# block_detector_schematic.net
KiCad netlist of a schematic drawn in EasyEDA
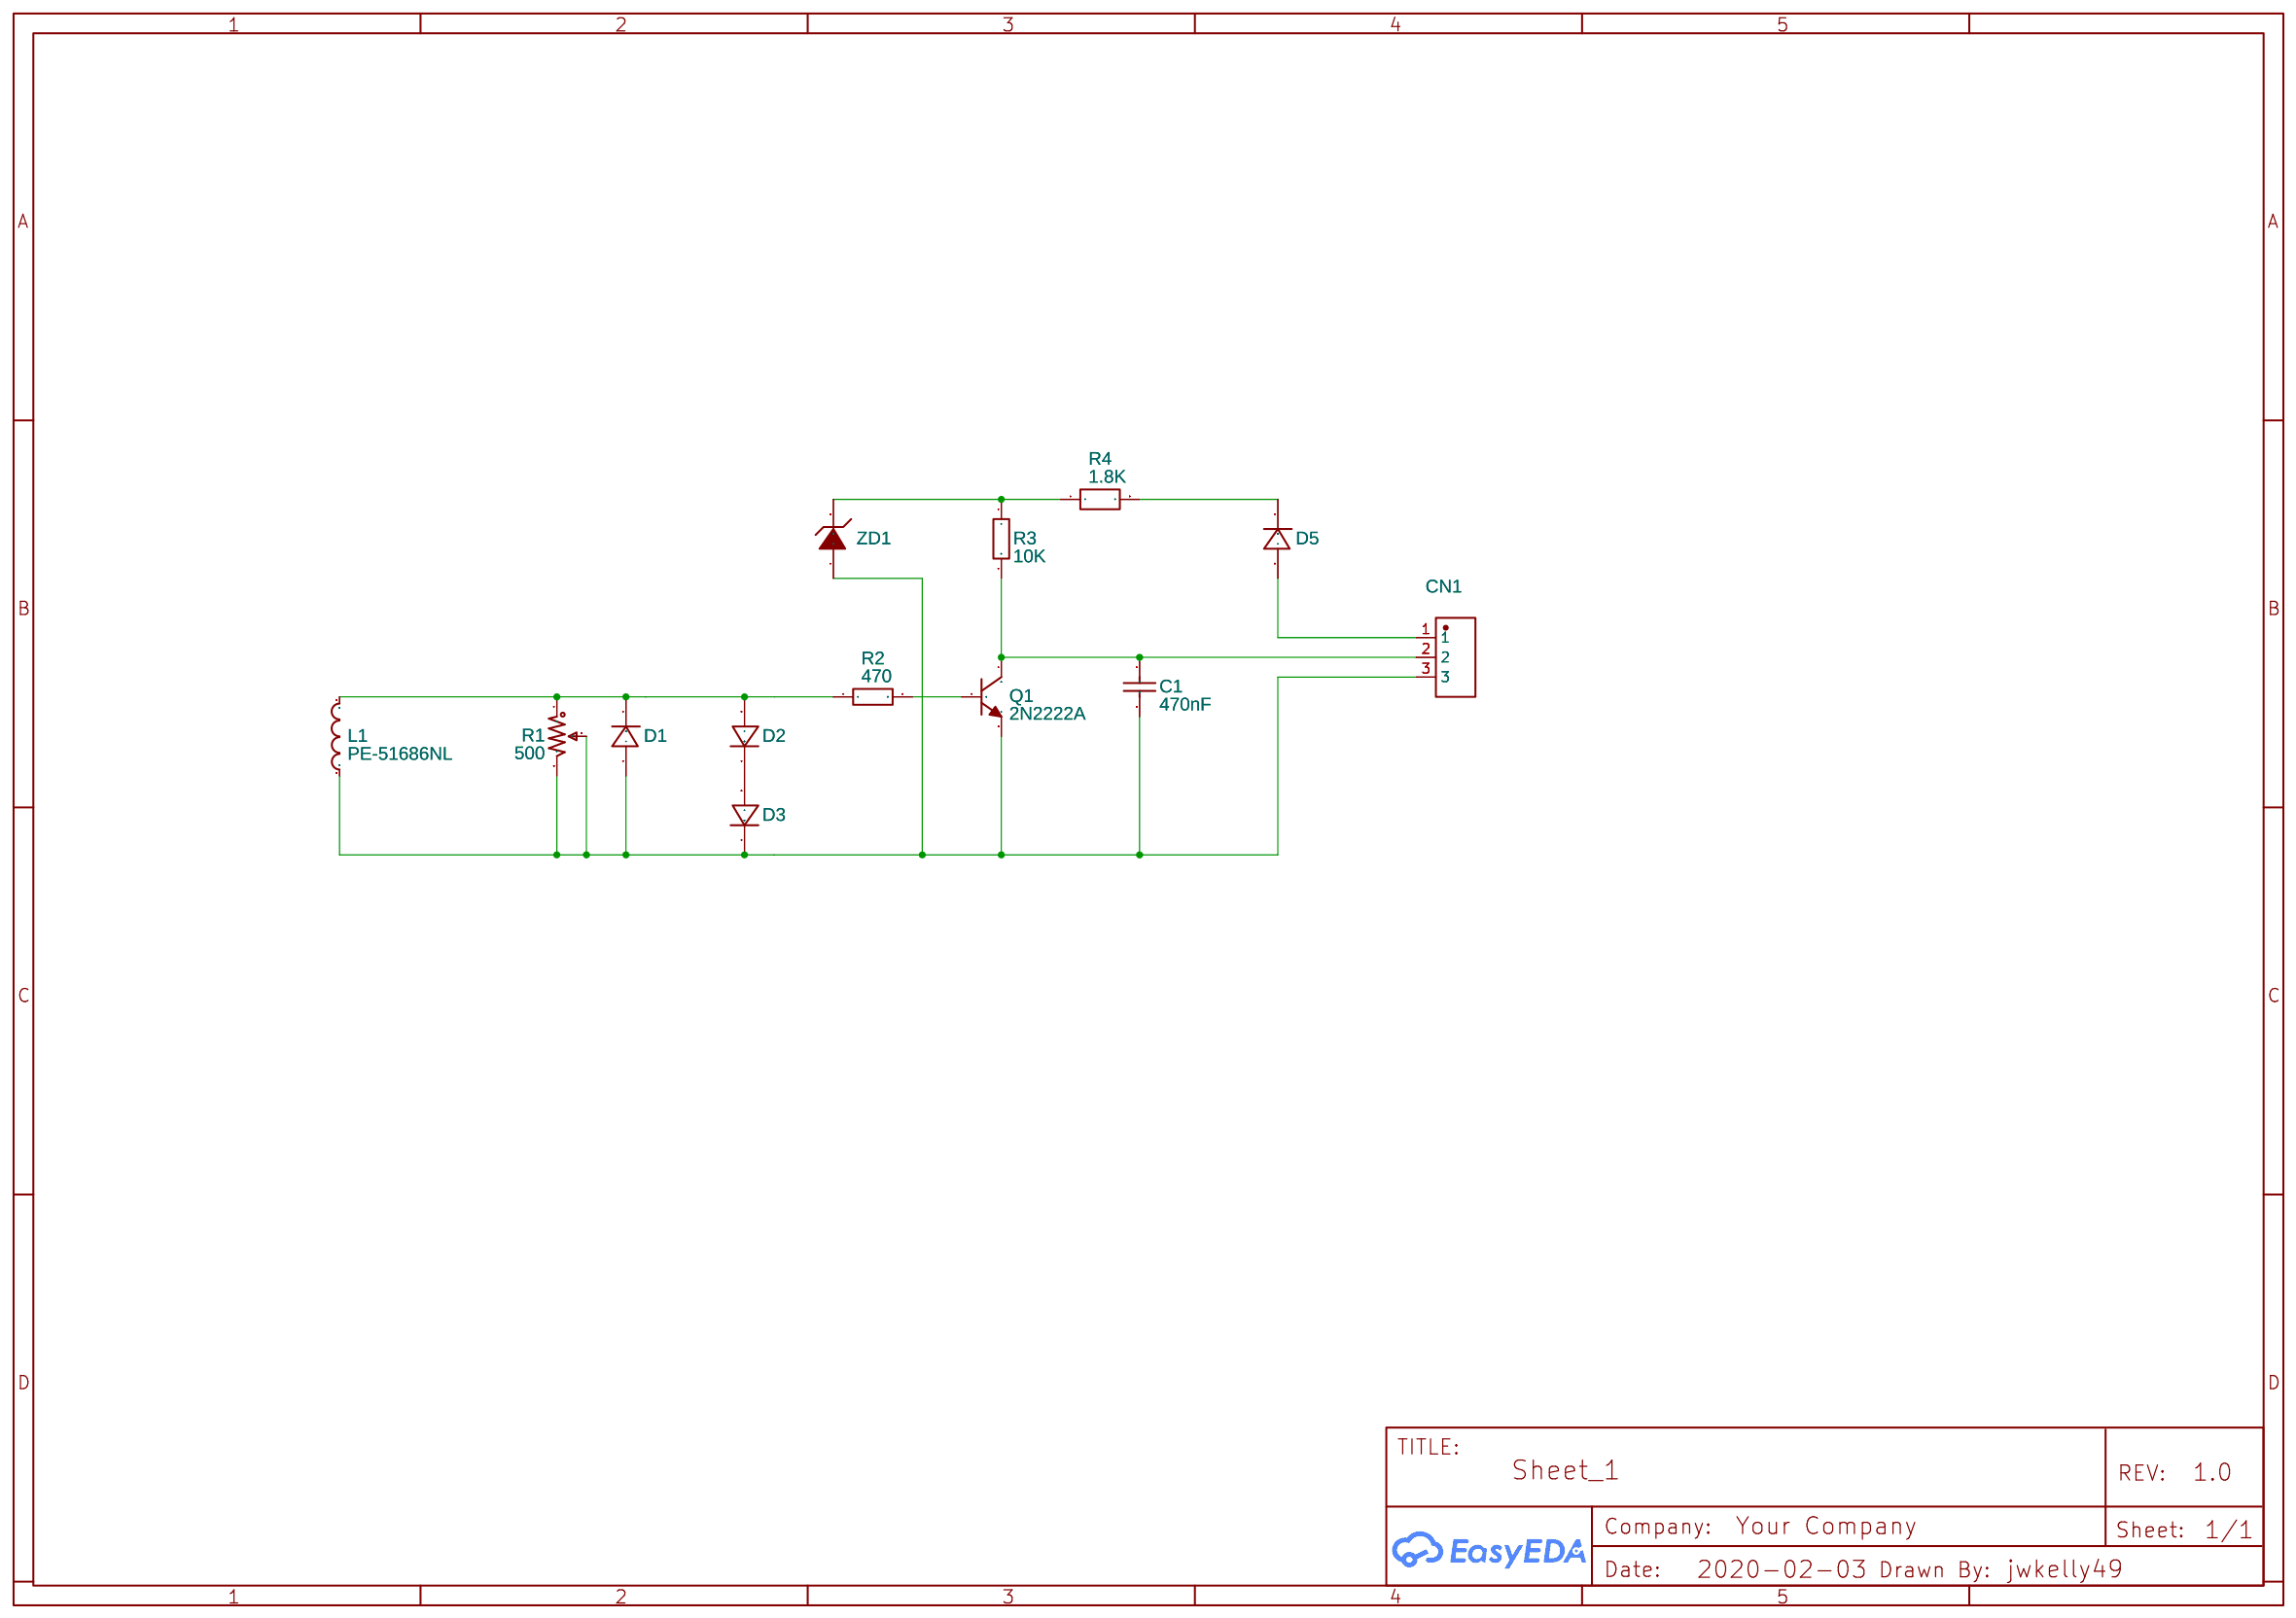
[diagram p0: schematic sheet]

(export (version "E")
  (design (tool "Eeschema 10.0.6"))
  (components
    (comp (ref "C1")
      (value "470nF")
      (fields
        (field (name "BOM_Manufacturer Part") "CT4-0805B474K500F3")
        (field (name "BOM_Supplier Part") "C93116")
      )
      (libsource (lib "") (part "CT4-0805B474K500F3"))
    )
    (comp (ref "CN1")
      (value "WJ25C-B-7.62-3P-13-00A")
      (fields (field (name "BOM_Supplier Part") "C61583"))
      (libsource (lib "") (part "WJ25C-B-7.62-3P-13-00A"))
    )
    (comp (ref "D1")
      (value "1N4001_C331627")
      (fields (field (name "BOM_Manufacturer Part") "1N4001") (field (name "BOM_Supplier Part") "C331627"))
      (libsource (lib "") (part "1N4001_C331627_1"))
    )
    (comp (ref "D2")
      (value "1N4001_C331627")
      (fields (field (name "BOM_Manufacturer Part") "1N4001") (field (name "BOM_Supplier Part") "C331627"))
      (libsource (lib "") (part "1N4001_C331627"))
    )
    (comp (ref "D3")
      (value "1N4001_C331627")
      (fields (field (name "BOM_Manufacturer Part") "1N4001") (field (name "BOM_Supplier Part") "C331627"))
      (libsource (lib "") (part "1N4001_C331627"))
    )
    (comp (ref "D5")
      (value "1N4001_C331627")
      (fields (field (name "BOM_Manufacturer Part") "1N4001") (field (name "BOM_Supplier Part") "C331627"))
      (libsource (lib "") (part "1N4001_C331627_1"))
    )
    (comp (ref "L1")
      (value "PE-51686NL")
      (fields (field (name "BOM_Manufacturer Part") "ZMCT102") (field (name "BOM_Supplier Part") "C84213"))
      (libsource (lib "") (part "ZMCT102"))
    )
    (comp (ref "Q1")
      (value "2N2222A")
      (fields (field (name "BOM_Supplier Part") "C358533"))
      (libsource (lib "") (part "2N2222A"))
    )
    (comp (ref "R1")
      (value "500")
      (fields
        (field (name "BOM_Manufacturer Part") "3362S-1-501LF")
        (field (name "BOM_Supplier Part") "C81261")
      )
      (libsource (lib "") (part "3362S-1-501LF"))
    )
    (comp (ref "R2")
      (value "470")
      (fields (field (name "BOM_Supplier Part") "C120047"))
      (libsource (lib "") (part "CF1/4W-470Ω±5% T52"))
    )
    (comp (ref "R3")
      (value "10K")
      (fields
        (field (name "BOM_Manufacturer Part") "CFR0W4J0103A50")
        (field (name "BOM_Supplier Part") "C61299")
      )
      (libsource (lib "") (part "CFR0W4J0103A50"))
    )
    (comp (ref "R4")
      (value "1.8K")
      (fields
        (field (name "BOM_Manufacturer Part") "RD 1/4W 1K8 J T/B A1")
        (field (name "BOM_Supplier Part") "C433758")
      )
      (libsource (lib "") (part "RD 1/4W 1K8 J T/B A1"))
    )
    (comp (ref "ZD1")
      (value "1N4734A_C41430")
      (fields (field (name "BOM_Manufacturer Part") "1N4734A") (field (name "BOM_Supplier Part") "C41430"))
      (libsource (lib "") (part "1N4734A_C41430"))
    )
  )
  (nets
    (net (code "1") (name "Net-(D1-A)") (class "Default")
      (node (ref "C1") (pin "2") (pinfunction "2_2") (pintype "input"))
      (node (ref "CN1") (pin "3") (pinfunction "3_3") (pintype "unspecified"))
      (node (ref "D1") (pin "2") (pinfunction "A_2") (pintype "unspecified"))
      (node (ref "D3") (pin "1") (pinfunction "C_1") (pintype "unspecified"))
      (node (ref "L1") (pin "1") (pinfunction "1_1") (pintype "unspecified"))
      (node (ref "Q1") (pin "3") (pinfunction "E_3") (pintype "unspecified"))
      (node (ref "R1") (pin "2") (pinfunction "2_2") (pintype "unspecified"))
      (node (ref "R1") (pin "3") (pinfunction "3_3") (pintype "unspecified"))
      (node (ref "ZD1") (pin "1") (pinfunction "A_1") (pintype "unspecified"))
    )
    (net (code "2") (name "Net-(D1-C)") (class "Default")
      (node (ref "D1") (pin "1") (pinfunction "C_1") (pintype "unspecified"))
      (node (ref "D2") (pin "2") (pinfunction "A_2") (pintype "unspecified"))
      (node (ref "L1") (pin "2") (pinfunction "2_2") (pintype "unspecified"))
      (node (ref "R1") (pin "1") (pinfunction "1_1") (pintype "unspecified"))
      (node (ref "R2") (pin "1") (pinfunction "1_1") (pintype "unspecified"))
    )
    (net (code "3") (name "Net-(D2-C)") (class "Default")
      (node (ref "D2") (pin "1") (pinfunction "C_1") (pintype "unspecified"))
      (node (ref "D3") (pin "2") (pinfunction "A_2") (pintype "unspecified"))
    )
    (net (code "4") (name "Net-(D5-A)") (class "Default")
      (node (ref "CN1") (pin "1") (pinfunction "1_1") (pintype "unspecified"))
      (node (ref "D5") (pin "2") (pinfunction "A_2") (pintype "unspecified"))
    )
    (net (code "5") (name "Net-(D5-C)") (class "Default")
      (node (ref "D5") (pin "1") (pinfunction "C_1") (pintype "unspecified"))
      (node (ref "R4") (pin "2") (pinfunction "2_2") (pintype "unspecified"))
    )
    (net (code "6") (name "Net-(Q1-B)") (class "Default")
      (node (ref "Q1") (pin "2") (pinfunction "B_2") (pintype "unspecified"))
      (node (ref "R2") (pin "2") (pinfunction "2_2") (pintype "unspecified"))
    )
    (net (code "7") (name "Net-(Q1-C)") (class "Default")
      (node (ref "C1") (pin "1") (pinfunction "1_1") (pintype "input"))
      (node (ref "CN1") (pin "2") (pinfunction "2_2") (pintype "unspecified"))
      (node (ref "Q1") (pin "1") (pinfunction "C_1") (pintype "unspecified"))
      (node (ref "R3") (pin "2") (pinfunction "2_2") (pintype "input"))
    )
    (net (code "8") (name "Net-(ZD1-K)") (class "Default")
      (node (ref "R3") (pin "1") (pinfunction "1_1") (pintype "input"))
      (node (ref "R4") (pin "1") (pinfunction "1_1") (pintype "unspecified"))
      (node (ref "ZD1") (pin "2") (pinfunction "K_2") (pintype "unspecified"))
    )
  )
)
